# I2C_shifter.net
KiCad netlist of a schematic drawn in EAGLE
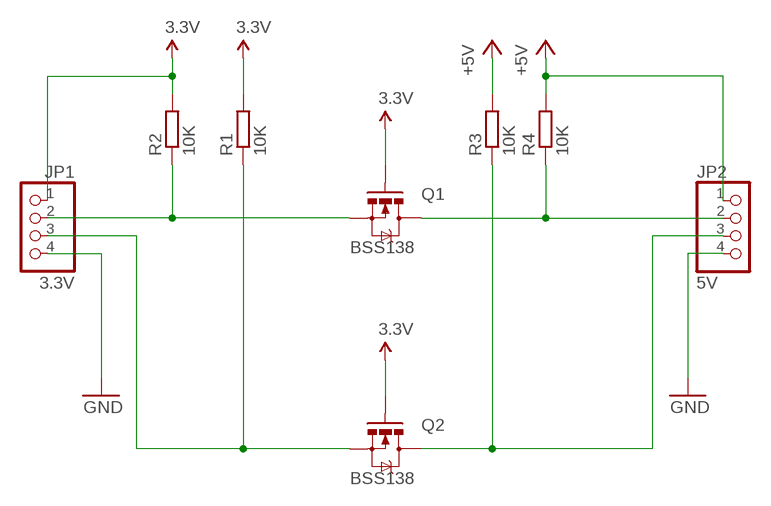
[diagram p0: schematic, sheet 1]

(export (version "E")
  (design (tool "Eeschema 10.0.6"))
  (components
    (comp (ref "JP1")
      (value "3.3V")
      (footprint "eagle-import:1X04")
      (libsource (lib "eagle-import") (part "PINHD-1X4"))
    )
    (comp (ref "JP2")
      (value "5V")
      (footprint "eagle-import:1X04")
      (libsource (lib "eagle-import") (part "PINHD-1X4"))
    )
    (comp (ref "Q1")
      (value "BSS138")
      (footprint "eagle-import:SOT23-3")
      (libsource (lib "eagle-import") (part "MOSFET-NCHANNELBSS138"))
    )
    (comp (ref "Q2")
      (value "BSS138")
      (footprint "eagle-import:SOT23-3")
      (libsource (lib "eagle-import") (part "MOSFET-NCHANNELBSS138"))
    )
    (comp (ref "R1")
      (value "10K")
      (footprint "eagle-import:M1206")
      (libsource (lib "eagle-import") (part "R-EU_M1206"))
    )
    (comp (ref "R2")
      (value "10K")
      (footprint "eagle-import:M1206")
      (libsource (lib "eagle-import") (part "R-EU_M1206"))
    )
    (comp (ref "R3")
      (value "10K")
      (footprint "eagle-import:M1206")
      (libsource (lib "eagle-import") (part "R-EU_M1206"))
    )
    (comp (ref "R4")
      (value "10K")
      (footprint "eagle-import:M1206")
      (libsource (lib "eagle-import") (part "R-EU_M1206"))
    )
  )
  (nets
    (net (code "1") (name "+5V") (class "Default")
      (node (ref "JP2") (pin "1") (pinfunction "1_1") (pintype "passive"))
      (node (ref "R3") (pin "2") (pinfunction "2_2") (pintype "passive"))
      (node (ref "R4") (pin "2") (pinfunction "2_2") (pintype "passive"))
    )
    (net (code "2") (name "3.3V") (class "Default")
      (node (ref "JP1") (pin "1") (pinfunction "1_1") (pintype "passive"))
      (node (ref "Q1") (pin "1") (pinfunction "G_1") (pintype "passive"))
      (node (ref "Q2") (pin "1") (pinfunction "G_1") (pintype "passive"))
      (node (ref "R1") (pin "2") (pinfunction "2_2") (pintype "passive"))
      (node (ref "R2") (pin "2") (pinfunction "2_2") (pintype "passive"))
    )
    (net (code "3") (name "GND") (class "Default")
      (node (ref "JP1") (pin "4") (pinfunction "4_4") (pintype "passive"))
      (node (ref "JP2") (pin "4") (pinfunction "4_4") (pintype "passive"))
    )
    (net (code "4") (name "Net-(Q1-D)") (class "Default")
      (node (ref "JP2") (pin "2") (pinfunction "2_2") (pintype "passive"))
      (node (ref "Q1") (pin "3") (pinfunction "D_3") (pintype "passive"))
      (node (ref "R4") (pin "1") (pinfunction "1_1") (pintype "passive"))
    )
    (net (code "5") (name "Net-(Q1-S)") (class "Default")
      (node (ref "JP1") (pin "2") (pinfunction "2_2") (pintype "passive"))
      (node (ref "Q1") (pin "2") (pinfunction "S_2") (pintype "passive"))
      (node (ref "R2") (pin "1") (pinfunction "1_1") (pintype "passive"))
    )
    (net (code "6") (name "Net-(Q2-D)") (class "Default")
      (node (ref "JP2") (pin "3") (pinfunction "3_3") (pintype "passive"))
      (node (ref "Q2") (pin "3") (pinfunction "D_3") (pintype "passive"))
      (node (ref "R3") (pin "1") (pinfunction "1_1") (pintype "passive"))
    )
    (net (code "7") (name "Net-(Q2-S)") (class "Default")
      (node (ref "JP1") (pin "3") (pinfunction "3_3") (pintype "passive"))
      (node (ref "Q2") (pin "2") (pinfunction "S_2") (pintype "passive"))
      (node (ref "R1") (pin "1") (pinfunction "1_1") (pintype "passive"))
    )
  )
)
